# NEW_MAIN.net
KiCad netlist of a schematic drawn in EAGLE
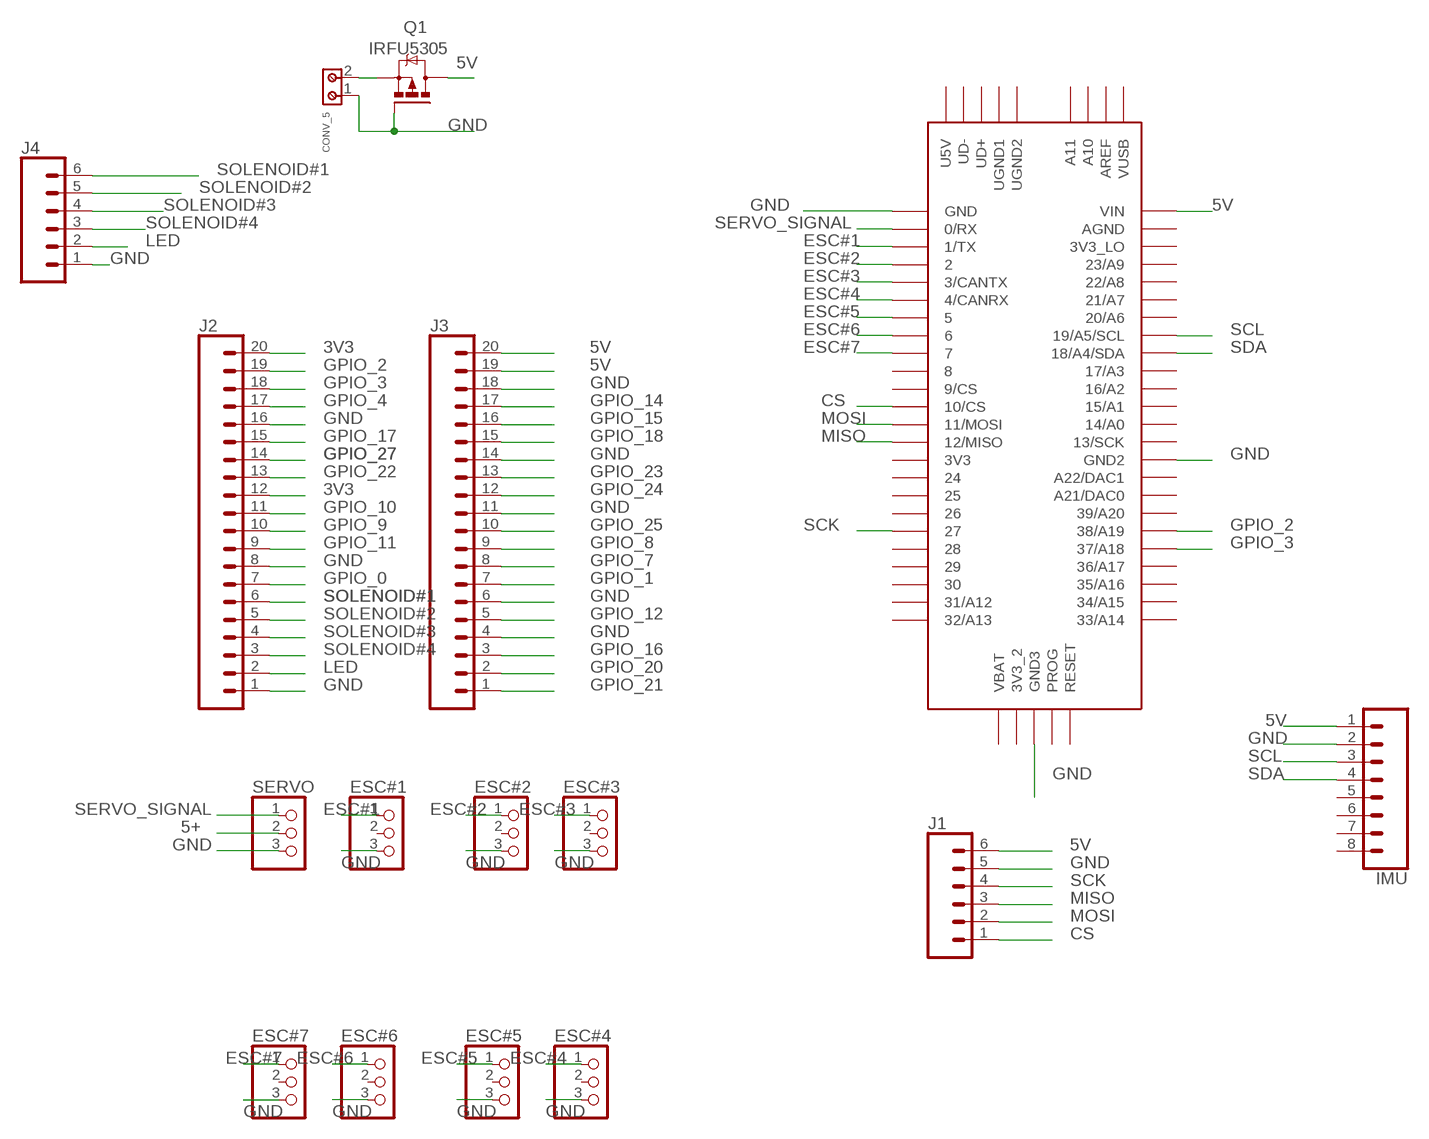
[diagram p0: schematic, sheet 1]

(export (version "E")
  (design (tool "Eeschema 10.0.6"))
  (components
    (comp (ref "CONV_5")
      (value "691213500002")
      (footprint "eagle-import:691213500002")
      (libsource (lib "eagle-import") (part "691213500002"))
    )
    (comp (ref "ESC#1")
      (value "PINHD-1X3")
      (footprint "eagle-import:1X03")
      (libsource (lib "eagle-import") (part "PINHD-1X3"))
    )
    (comp (ref "ESC#2")
      (value "PINHD-1X3")
      (footprint "eagle-import:1X03")
      (libsource (lib "eagle-import") (part "PINHD-1X3"))
    )
    (comp (ref "ESC#3")
      (value "PINHD-1X3")
      (footprint "eagle-import:1X03")
      (libsource (lib "eagle-import") (part "PINHD-1X3"))
    )
    (comp (ref "ESC#4")
      (value "PINHD-1X3")
      (footprint "eagle-import:1X03")
      (libsource (lib "eagle-import") (part "PINHD-1X3"))
    )
    (comp (ref "ESC#5")
      (value "PINHD-1X3")
      (footprint "eagle-import:1X03")
      (libsource (lib "eagle-import") (part "PINHD-1X3"))
    )
    (comp (ref "ESC#6")
      (value "PINHD-1X3")
      (footprint "eagle-import:1X03")
      (libsource (lib "eagle-import") (part "PINHD-1X3"))
    )
    (comp (ref "ESC#7")
      (value "PINHD-1X3")
      (footprint "eagle-import:1X03")
      (libsource (lib "eagle-import") (part "PINHD-1X3"))
    )
    (comp (ref "IMU")
      (value "CONN_08\"")
      (footprint "eagle-import:1X08")
      (libsource (lib "eagle-import") (part "CONN_08{dblquote}"))
    )
    (comp (ref "J1")
      (value "CONN_06LOCK")
      (footprint "eagle-import:1X06_LOCK")
      (libsource (lib "eagle-import") (part "CONN_06LOCK"))
    )
    (comp (ref "J2")
      (value "CONN_20")
      (footprint "eagle-import:1X20")
      (libsource (lib "eagle-import") (part "CONN_20"))
    )
    (comp (ref "J3")
      (value "CONN_20")
      (footprint "eagle-import:1X20")
      (libsource (lib "eagle-import") (part "CONN_20"))
    )
    (comp (ref "J4")
      (value "CONN_06FEMALE_LOCK")
      (footprint "eagle-import:1X06_FEMALE_LOCK.010")
      (libsource (lib "eagle-import") (part "CONN_06FEMALE_LOCK"))
    )
    (comp (ref "Q1")
      (value "IRFU5305")
      (footprint "eagle-import:I-PAK_TO251AA")
      (libsource (lib "eagle-import") (part "IRF?5305U"))
    )
    (comp (ref "SERVO")
      (value "PINHD-1X3")
      (footprint "eagle-import:1X03")
      (libsource (lib "eagle-import") (part "PINHD-1X3"))
    )
    (comp (ref "U$1")
      (value "TEENSY_3.5/3.6")
      (footprint "eagle-import:TEENSY_3.5_3.6")
      (libsource (lib "eagle-import") (part "TEENSY_3.5/3.6"))
    )
  )
  (nets
    (net (code "1") (name "/3V3") (class "Default")
      (node (ref "J2") (pin "12") (pinfunction "12_12") (pintype "passive"))
      (node (ref "J2") (pin "20") (pinfunction "20_20") (pintype "passive"))
    )
    (net (code "2") (name "/5+") (class "Default")
      (node (ref "SERVO") (pin "2") (pinfunction "2_2") (pintype "passive"))
    )
    (net (code "3") (name "/5V") (class "Default")
      (node (ref "IMU") (pin "1") (pinfunction "1_1") (pintype "passive"))
      (node (ref "J1") (pin "6") (pinfunction "6_6") (pintype "passive"))
      (node (ref "J3") (pin "19") (pinfunction "19_19") (pintype "passive"))
      (node (ref "J3") (pin "20") (pinfunction "20_20") (pintype "passive"))
      (node (ref "Q1") (pin "2") (pinfunction "D_2") (pintype "passive"))
      (node (ref "U$1") (pin "VIN") (pinfunction "VIN_VIN") (pintype "bidirectional"))
    )
    (net (code "4") (name "/CS") (class "Default")
      (node (ref "J1") (pin "1") (pinfunction "1_1") (pintype "passive"))
      (node (ref "U$1") (pin "10/CS") (pinfunction "10/CS_10/CS") (pintype "bidirectional"))
    )
    (net (code "5") (name "/ESC#1") (class "Default")
      (node (ref "ESC#1") (pin "1") (pinfunction "1_1") (pintype "passive"))
      (node (ref "U$1") (pin "1/TX") (pinfunction "1/TX_1/TX") (pintype "bidirectional"))
    )
    (net (code "6") (name "/ESC#2") (class "Default")
      (node (ref "ESC#2") (pin "1") (pinfunction "1_1") (pintype "passive"))
      (node (ref "U$1") (pin "2") (pinfunction "2_2") (pintype "bidirectional"))
    )
    (net (code "7") (name "/ESC#3") (class "Default")
      (node (ref "ESC#3") (pin "1") (pinfunction "1_1") (pintype "passive"))
      (node (ref "U$1") (pin "3/CANTX") (pinfunction "3/CANTX_3/CANTX") (pintype "bidirectional"))
    )
    (net (code "8") (name "/ESC#4") (class "Default")
      (node (ref "ESC#4") (pin "1") (pinfunction "1_1") (pintype "passive"))
      (node (ref "U$1") (pin "4/CANRX") (pinfunction "4/CANRX_4/CANRX") (pintype "bidirectional"))
    )
    (net (code "9") (name "/ESC#5") (class "Default")
      (node (ref "ESC#5") (pin "1") (pinfunction "1_1") (pintype "passive"))
      (node (ref "U$1") (pin "5") (pinfunction "5_5") (pintype "bidirectional"))
    )
    (net (code "10") (name "/ESC#6") (class "Default")
      (node (ref "ESC#6") (pin "1") (pinfunction "1_1") (pintype "passive"))
      (node (ref "U$1") (pin "6") (pinfunction "6_6") (pintype "bidirectional"))
    )
    (net (code "11") (name "/ESC#7") (class "Default")
      (node (ref "ESC#7") (pin "1") (pinfunction "1_1") (pintype "passive"))
      (node (ref "U$1") (pin "7") (pinfunction "7_7") (pintype "bidirectional"))
    )
    (net (code "12") (name "/GND") (class "Default")
      (node (ref "CONV_5") (pin "1") (pinfunction "1_1") (pintype "passive"))
      (node (ref "ESC#1") (pin "3") (pinfunction "3_3") (pintype "passive"))
      (node (ref "ESC#2") (pin "3") (pinfunction "3_3") (pintype "passive"))
      (node (ref "ESC#3") (pin "3") (pinfunction "3_3") (pintype "passive"))
      (node (ref "ESC#4") (pin "3") (pinfunction "3_3") (pintype "passive"))
      (node (ref "ESC#5") (pin "3") (pinfunction "3_3") (pintype "passive"))
      (node (ref "ESC#6") (pin "3") (pinfunction "3_3") (pintype "passive"))
      (node (ref "ESC#7") (pin "3") (pinfunction "3_3") (pintype "passive"))
      (node (ref "IMU") (pin "2") (pinfunction "2_2") (pintype "passive"))
      (node (ref "J1") (pin "5") (pinfunction "5_5") (pintype "passive"))
      (node (ref "J2") (pin "1") (pinfunction "1_1") (pintype "passive"))
      (node (ref "J2") (pin "16") (pinfunction "16_16") (pintype "passive"))
      (node (ref "J2") (pin "8") (pinfunction "8_8") (pintype "passive"))
      (node (ref "J3") (pin "11") (pinfunction "11_11") (pintype "passive"))
      (node (ref "J3") (pin "14") (pinfunction "14_14") (pintype "passive"))
      (node (ref "J3") (pin "18") (pinfunction "18_18") (pintype "passive"))
      (node (ref "J3") (pin "4") (pinfunction "4_4") (pintype "passive"))
      (node (ref "J3") (pin "6") (pinfunction "6_6") (pintype "passive"))
      (node (ref "J4") (pin "1") (pinfunction "1_1") (pintype "passive"))
      (node (ref "Q1") (pin "1") (pinfunction "G_1") (pintype "passive"))
      (node (ref "SERVO") (pin "3") (pinfunction "3_3") (pintype "passive"))
      (node (ref "U$1") (pin "GND") (pinfunction "GND_GND") (pintype "bidirectional"))
      (node (ref "U$1") (pin "GND2") (pinfunction "GND2_GND2") (pintype "bidirectional"))
      (node (ref "U$1") (pin "GND3") (pinfunction "GND3_GND3") (pintype "bidirectional"))
    )
    (net (code "13") (name "/GPIO_0") (class "Default")
      (node (ref "J2") (pin "7") (pinfunction "7_7") (pintype "passive"))
    )
    (net (code "14") (name "/GPIO_1") (class "Default")
      (node (ref "J3") (pin "7") (pinfunction "7_7") (pintype "passive"))
    )
    (net (code "15") (name "/GPIO_2") (class "Default")
      (node (ref "J2") (pin "19") (pinfunction "19_19") (pintype "passive"))
      (node (ref "U$1") (pin "38/A19") (pinfunction "38/A19_38/A19") (pintype "bidirectional"))
    )
    (net (code "16") (name "/GPIO_3") (class "Default")
      (node (ref "J2") (pin "18") (pinfunction "18_18") (pintype "passive"))
      (node (ref "U$1") (pin "37/A18") (pinfunction "37/A18_37/A18") (pintype "bidirectional"))
    )
    (net (code "17") (name "/GPIO_4") (class "Default")
      (node (ref "J2") (pin "17") (pinfunction "17_17") (pintype "passive"))
    )
    (net (code "18") (name "/GPIO_7") (class "Default")
      (node (ref "J3") (pin "8") (pinfunction "8_8") (pintype "passive"))
    )
    (net (code "19") (name "/GPIO_8") (class "Default")
      (node (ref "J3") (pin "9") (pinfunction "9_9") (pintype "passive"))
    )
    (net (code "20") (name "/GPIO_9") (class "Default")
      (node (ref "J2") (pin "10") (pinfunction "10_10") (pintype "passive"))
    )
    (net (code "21") (name "/GPIO_10") (class "Default")
      (node (ref "J2") (pin "11") (pinfunction "11_11") (pintype "passive"))
    )
    (net (code "22") (name "/GPIO_11") (class "Default")
      (node (ref "J2") (pin "9") (pinfunction "9_9") (pintype "passive"))
    )
    (net (code "23") (name "/GPIO_12") (class "Default")
      (node (ref "J3") (pin "5") (pinfunction "5_5") (pintype "passive"))
    )
    (net (code "24") (name "/GPIO_14") (class "Default")
      (node (ref "J3") (pin "17") (pinfunction "17_17") (pintype "passive"))
    )
    (net (code "25") (name "/GPIO_15") (class "Default")
      (node (ref "J3") (pin "16") (pinfunction "16_16") (pintype "passive"))
    )
    (net (code "26") (name "/GPIO_16") (class "Default")
      (node (ref "J3") (pin "3") (pinfunction "3_3") (pintype "passive"))
    )
    (net (code "27") (name "/GPIO_17") (class "Default")
      (node (ref "J2") (pin "15") (pinfunction "15_15") (pintype "passive"))
    )
    (net (code "28") (name "/GPIO_18") (class "Default")
      (node (ref "J3") (pin "15") (pinfunction "15_15") (pintype "passive"))
    )
    (net (code "29") (name "/GPIO_20") (class "Default")
      (node (ref "J3") (pin "2") (pinfunction "2_2") (pintype "passive"))
    )
    (net (code "30") (name "/GPIO_21") (class "Default")
      (node (ref "J3") (pin "1") (pinfunction "1_1") (pintype "passive"))
    )
    (net (code "31") (name "/GPIO_22") (class "Default")
      (node (ref "J2") (pin "13") (pinfunction "13_13") (pintype "passive"))
    )
    (net (code "32") (name "/GPIO_23") (class "Default")
      (node (ref "J3") (pin "13") (pinfunction "13_13") (pintype "passive"))
    )
    (net (code "33") (name "/GPIO_24") (class "Default")
      (node (ref "J3") (pin "12") (pinfunction "12_12") (pintype "passive"))
    )
    (net (code "34") (name "/GPIO_25") (class "Default")
      (node (ref "J3") (pin "10") (pinfunction "10_10") (pintype "passive"))
    )
    (net (code "35") (name "/GPIO_27") (class "Default")
      (node (ref "J2") (pin "14") (pinfunction "14_14") (pintype "passive"))
    )
    (net (code "36") (name "/LED") (class "Default")
      (node (ref "J2") (pin "2") (pinfunction "2_2") (pintype "passive"))
      (node (ref "J4") (pin "2") (pinfunction "2_2") (pintype "passive"))
    )
    (net (code "37") (name "/MISO") (class "Default")
      (node (ref "J1") (pin "3") (pinfunction "3_3") (pintype "passive"))
      (node (ref "U$1") (pin "12/MISO") (pinfunction "12/MISO_12/MISO") (pintype "bidirectional"))
    )
    (net (code "38") (name "/MOSI") (class "Default")
      (node (ref "J1") (pin "2") (pinfunction "2_2") (pintype "passive"))
      (node (ref "U$1") (pin "11/MOSI") (pinfunction "11/MOSI_11/MOSI") (pintype "bidirectional"))
    )
    (net (code "39") (name "/SCK") (class "Default")
      (node (ref "J1") (pin "4") (pinfunction "4_4") (pintype "passive"))
      (node (ref "U$1") (pin "27") (pinfunction "27_27") (pintype "bidirectional"))
    )
    (net (code "40") (name "/SCL") (class "Default")
      (node (ref "IMU") (pin "3") (pinfunction "3_3") (pintype "passive"))
      (node (ref "U$1") (pin "19/A5/SCL") (pinfunction "19/A5/SCL_19/A5/SCL") (pintype "bidirectional"))
    )
    (net (code "41") (name "/SDA") (class "Default")
      (node (ref "IMU") (pin "4") (pinfunction "4_4") (pintype "passive"))
      (node (ref "U$1") (pin "18/A4/SDA") (pinfunction "18/A4/SDA_18/A4/SDA") (pintype "bidirectional"))
    )
    (net (code "42") (name "/SERVO_SIGNAL") (class "Default")
      (node (ref "SERVO") (pin "1") (pinfunction "1_1") (pintype "passive"))
      (node (ref "U$1") (pin "0/RX") (pinfunction "0/RX_0/RX") (pintype "bidirectional"))
    )
    (net (code "43") (name "/SOLENOID#1") (class "Default")
      (node (ref "J2") (pin "6") (pinfunction "6_6") (pintype "passive"))
      (node (ref "J4") (pin "6") (pinfunction "6_6") (pintype "passive"))
    )
    (net (code "44") (name "/SOLENOID#2") (class "Default")
      (node (ref "J2") (pin "5") (pinfunction "5_5") (pintype "passive"))
      (node (ref "J4") (pin "5") (pinfunction "5_5") (pintype "passive"))
    )
    (net (code "45") (name "/SOLENOID#3") (class "Default")
      (node (ref "J2") (pin "4") (pinfunction "4_4") (pintype "passive"))
      (node (ref "J4") (pin "4") (pinfunction "4_4") (pintype "passive"))
    )
    (net (code "46") (name "/SOLENOID#4") (class "Default")
      (node (ref "J2") (pin "3") (pinfunction "3_3") (pintype "passive"))
      (node (ref "J4") (pin "3") (pinfunction "3_3") (pintype "passive"))
    )
    (net (code "47") (name "Net-(Q1-S)") (class "Default")
      (node (ref "CONV_5") (pin "2") (pinfunction "2_2") (pintype "passive"))
      (node (ref "Q1") (pin "3") (pinfunction "S_3") (pintype "passive"))
    )
    (net (code "48") (name "unconnected-(ESC#1-Pad2)") (class "Default")
      (node (ref "ESC#1") (pin "2") (pinfunction "2_2") (pintype "passive"))
    )
    (net (code "49") (name "unconnected-(ESC#2-Pad2)") (class "Default")
      (node (ref "ESC#2") (pin "2") (pinfunction "2_2") (pintype "passive"))
    )
    (net (code "50") (name "unconnected-(ESC#3-Pad2)") (class "Default")
      (node (ref "ESC#3") (pin "2") (pinfunction "2_2") (pintype "passive"))
    )
    (net (code "51") (name "unconnected-(ESC#4-Pad2)") (class "Default")
      (node (ref "ESC#4") (pin "2") (pinfunction "2_2") (pintype "passive"))
    )
    (net (code "52") (name "unconnected-(ESC#5-Pad2)") (class "Default")
      (node (ref "ESC#5") (pin "2") (pinfunction "2_2") (pintype "passive"))
    )
    (net (code "53") (name "unconnected-(ESC#6-Pad2)") (class "Default")
      (node (ref "ESC#6") (pin "2") (pinfunction "2_2") (pintype "passive"))
    )
    (net (code "54") (name "unconnected-(ESC#7-Pad2)") (class "Default")
      (node (ref "ESC#7") (pin "2") (pinfunction "2_2") (pintype "passive"))
    )
    (net (code "55") (name "unconnected-(IMU-Pad5)") (class "Default")
      (node (ref "IMU") (pin "5") (pinfunction "5_5") (pintype "passive"))
    )
    (net (code "56") (name "unconnected-(IMU-Pad6)") (class "Default")
      (node (ref "IMU") (pin "6") (pinfunction "6_6") (pintype "passive"))
    )
    (net (code "57") (name "unconnected-(IMU-Pad7)") (class "Default")
      (node (ref "IMU") (pin "7") (pinfunction "7_7") (pintype "passive"))
    )
    (net (code "58") (name "unconnected-(IMU-Pad8)") (class "Default")
      (node (ref "IMU") (pin "8") (pinfunction "8_8") (pintype "passive"))
    )
    (net (code "59") (name "unconnected-(U$1-A21{slash}DAC0-Pad21{slash}DAC0)") (class "Default")
      (node (ref "U$1") (pin "21/DAC0") (pinfunction "A21/DAC0_21/DAC0") (pintype "bidirectional"))
    )
    (net (code "60") (name "unconnected-(U$1-Pad3V3)") (class "Default")
      (node (ref "U$1") (pin "3V3") (pinfunction "3V3_3V3") (pintype "bidirectional"))
    )
    (net (code "61") (name "unconnected-(U$1-Pad3V3_2)") (class "Default")
      (node (ref "U$1") (pin "3V3_2") (pinfunction "3V3_2_3V3_2") (pintype "bidirectional"))
    )
    (net (code "62") (name "unconnected-(U$1-Pad3V3_LO)") (class "Default")
      (node (ref "U$1") (pin "3V3_LO") (pinfunction "3V3_LO_3V3_LO") (pintype "bidirectional"))
    )
    (net (code "63") (name "unconnected-(U$1-Pad8)") (class "Default")
      (node (ref "U$1") (pin "8") (pinfunction "8_8") (pintype "bidirectional"))
    )
    (net (code "64") (name "unconnected-(U$1-Pad9{slash}CS)") (class "Default")
      (node (ref "U$1") (pin "9/CS") (pinfunction "9/CS_9/CS") (pintype "bidirectional"))
    )
    (net (code "65") (name "unconnected-(U$1-Pad13{slash}SCK)") (class "Default")
      (node (ref "U$1") (pin "13/SCK") (pinfunction "13/SCK_13/SCK") (pintype "bidirectional"))
    )
    (net (code "66") (name "unconnected-(U$1-Pad14{slash}A0)") (class "Default")
      (node (ref "U$1") (pin "14/A0") (pinfunction "14/A0_14/A0") (pintype "bidirectional"))
    )
    (net (code "67") (name "unconnected-(U$1-Pad15{slash}A1)") (class "Default")
      (node (ref "U$1") (pin "15/A1") (pinfunction "15/A1_15/A1") (pintype "bidirectional"))
    )
    (net (code "68") (name "unconnected-(U$1-Pad16{slash}A2)") (class "Default")
      (node (ref "U$1") (pin "16/A2") (pinfunction "16/A2_16/A2") (pintype "bidirectional"))
    )
    (net (code "69") (name "unconnected-(U$1-Pad17{slash}A3)") (class "Default")
      (node (ref "U$1") (pin "17/A3") (pinfunction "17/A3_17/A3") (pintype "bidirectional"))
    )
    (net (code "70") (name "unconnected-(U$1-Pad20{slash}A6)") (class "Default")
      (node (ref "U$1") (pin "20/A6") (pinfunction "20/A6_20/A6") (pintype "bidirectional"))
    )
    (net (code "71") (name "unconnected-(U$1-Pad21{slash}A7)") (class "Default")
      (node (ref "U$1") (pin "21/A7") (pinfunction "21/A7_21/A7") (pintype "bidirectional"))
    )
    (net (code "72") (name "unconnected-(U$1-Pad22{slash}A8)") (class "Default")
      (node (ref "U$1") (pin "22/A8") (pinfunction "22/A8_22/A8") (pintype "bidirectional"))
    )
    (net (code "73") (name "unconnected-(U$1-Pad23{slash}A9)") (class "Default")
      (node (ref "U$1") (pin "23/A9") (pinfunction "23/A9_23/A9") (pintype "bidirectional"))
    )
    (net (code "74") (name "unconnected-(U$1-Pad24)") (class "Default")
      (node (ref "U$1") (pin "24") (pinfunction "24_24") (pintype "bidirectional"))
    )
    (net (code "75") (name "unconnected-(U$1-Pad25)") (class "Default")
      (node (ref "U$1") (pin "25") (pinfunction "25_25") (pintype "bidirectional"))
    )
    (net (code "76") (name "unconnected-(U$1-Pad26)") (class "Default")
      (node (ref "U$1") (pin "26") (pinfunction "26_26") (pintype "bidirectional"))
    )
    (net (code "77") (name "unconnected-(U$1-Pad28)") (class "Default")
      (node (ref "U$1") (pin "28") (pinfunction "28_28") (pintype "bidirectional"))
    )
    (net (code "78") (name "unconnected-(U$1-Pad29)") (class "Default")
      (node (ref "U$1") (pin "29") (pinfunction "29_29") (pintype "bidirectional"))
    )
    (net (code "79") (name "unconnected-(U$1-Pad30)") (class "Default")
      (node (ref "U$1") (pin "30") (pinfunction "30_30") (pintype "bidirectional"))
    )
    (net (code "80") (name "unconnected-(U$1-Pad31{slash}A12)") (class "Default")
      (node (ref "U$1") (pin "31/A12") (pinfunction "31/A12_31/A12") (pintype "bidirectional"))
    )
    (net (code "81") (name "unconnected-(U$1-Pad32{slash}A13)") (class "Default")
      (node (ref "U$1") (pin "32/A13") (pinfunction "32/A13_32/A13") (pintype "bidirectional"))
    )
    (net (code "82") (name "unconnected-(U$1-Pad33{slash}A14)") (class "Default")
      (node (ref "U$1") (pin "33/A14") (pinfunction "33/A14_33/A14") (pintype "bidirectional"))
    )
    (net (code "83") (name "unconnected-(U$1-Pad34{slash}A15)") (class "Default")
      (node (ref "U$1") (pin "34/A15") (pinfunction "34/A15_34/A15") (pintype "bidirectional"))
    )
    (net (code "84") (name "unconnected-(U$1-Pad35{slash}A16)") (class "Default")
      (node (ref "U$1") (pin "35/A16") (pinfunction "35/A16_35/A16") (pintype "bidirectional"))
    )
    (net (code "85") (name "unconnected-(U$1-Pad36{slash}A17)") (class "Default")
      (node (ref "U$1") (pin "36/A17") (pinfunction "36/A17_36/A17") (pintype "bidirectional"))
    )
    (net (code "86") (name "unconnected-(U$1-Pad39{slash}A20)") (class "Default")
      (node (ref "U$1") (pin "39/A20") (pinfunction "39/A20_39/A20") (pintype "bidirectional"))
    )
    (net (code "87") (name "unconnected-(U$1-PadA10)") (class "Default")
      (node (ref "U$1") (pin "A10") (pinfunction "A10_A10") (pintype "bidirectional"))
    )
    (net (code "88") (name "unconnected-(U$1-PadA11)") (class "Default")
      (node (ref "U$1") (pin "A11") (pinfunction "A11_A11") (pintype "bidirectional"))
    )
    (net (code "89") (name "unconnected-(U$1-PadA22{slash}DAC1)") (class "Default")
      (node (ref "U$1") (pin "A22/DAC1") (pinfunction "A22/DAC1_A22/DAC1") (pintype "bidirectional"))
    )
    (net (code "90") (name "unconnected-(U$1-PadAGND)") (class "Default")
      (node (ref "U$1") (pin "AGND") (pinfunction "AGND_AGND") (pintype "bidirectional"))
    )
    (net (code "91") (name "unconnected-(U$1-PadAREF)") (class "Default")
      (node (ref "U$1") (pin "AREF") (pinfunction "AREF_AREF") (pintype "bidirectional"))
    )
    (net (code "92") (name "unconnected-(U$1-PadPROG)") (class "Default")
      (node (ref "U$1") (pin "PROG") (pinfunction "PROG_PROG") (pintype "bidirectional"))
    )
    (net (code "93") (name "unconnected-(U$1-PadRESET)") (class "Default")
      (node (ref "U$1") (pin "RESET") (pinfunction "RESET_RESET") (pintype "bidirectional"))
    )
    (net (code "94") (name "unconnected-(U$1-PadU5V)") (class "Default")
      (node (ref "U$1") (pin "U5V") (pinfunction "U5V_U5V") (pintype "bidirectional"))
    )
    (net (code "95") (name "unconnected-(U$1-PadUD+)") (class "Default")
      (node (ref "U$1") (pin "UD+") (pinfunction "UD+_UD+") (pintype "bidirectional"))
    )
    (net (code "96") (name "unconnected-(U$1-PadUD-)") (class "Default")
      (node (ref "U$1") (pin "UD-") (pinfunction "UD-_UD-") (pintype "bidirectional"))
    )
    (net (code "97") (name "unconnected-(U$1-PadUGND1)") (class "Default")
      (node (ref "U$1") (pin "UGND1") (pinfunction "UGND1_UGND1") (pintype "bidirectional"))
    )
    (net (code "98") (name "unconnected-(U$1-PadUGND2)") (class "Default")
      (node (ref "U$1") (pin "UGND2") (pinfunction "UGND2_UGND2") (pintype "bidirectional"))
    )
    (net (code "99") (name "unconnected-(U$1-PadVBAT)") (class "Default")
      (node (ref "U$1") (pin "VBAT") (pinfunction "VBAT_VBAT") (pintype "bidirectional"))
    )
    (net (code "100") (name "unconnected-(U$1-PadVUSB)") (class "Default")
      (node (ref "U$1") (pin "VUSB") (pinfunction "VUSB_VUSB") (pintype "bidirectional"))
    )
  )
)
